# ASIC_2.net
KiCad netlist of a schematic drawn in Altium Designer
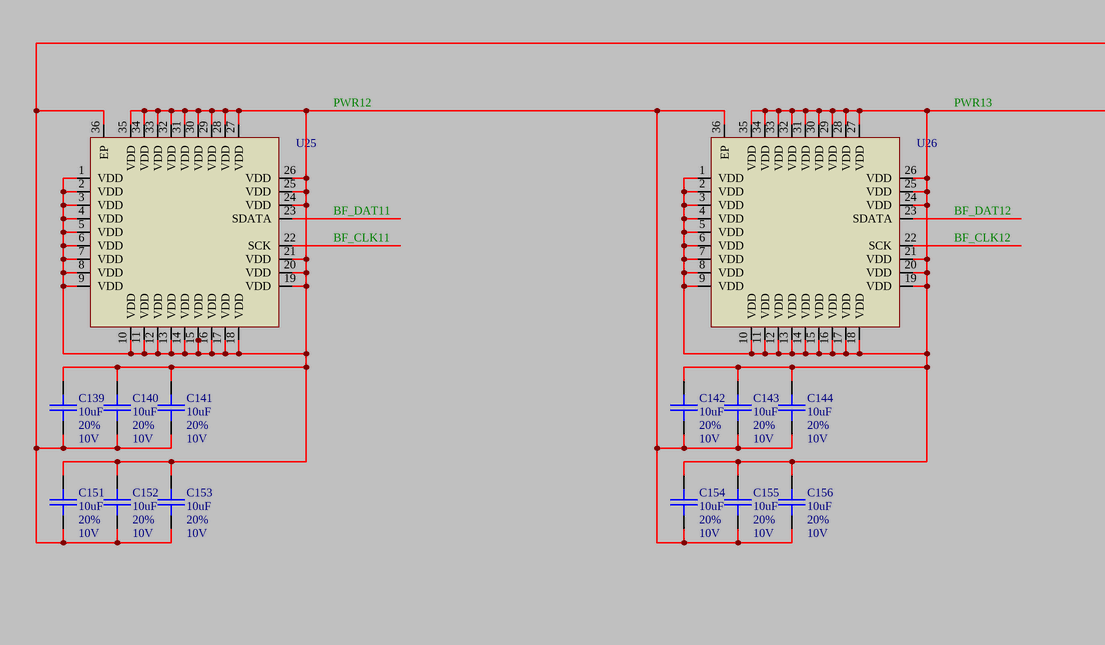
[diagram p0: ASIC_2.SchDoc, left]
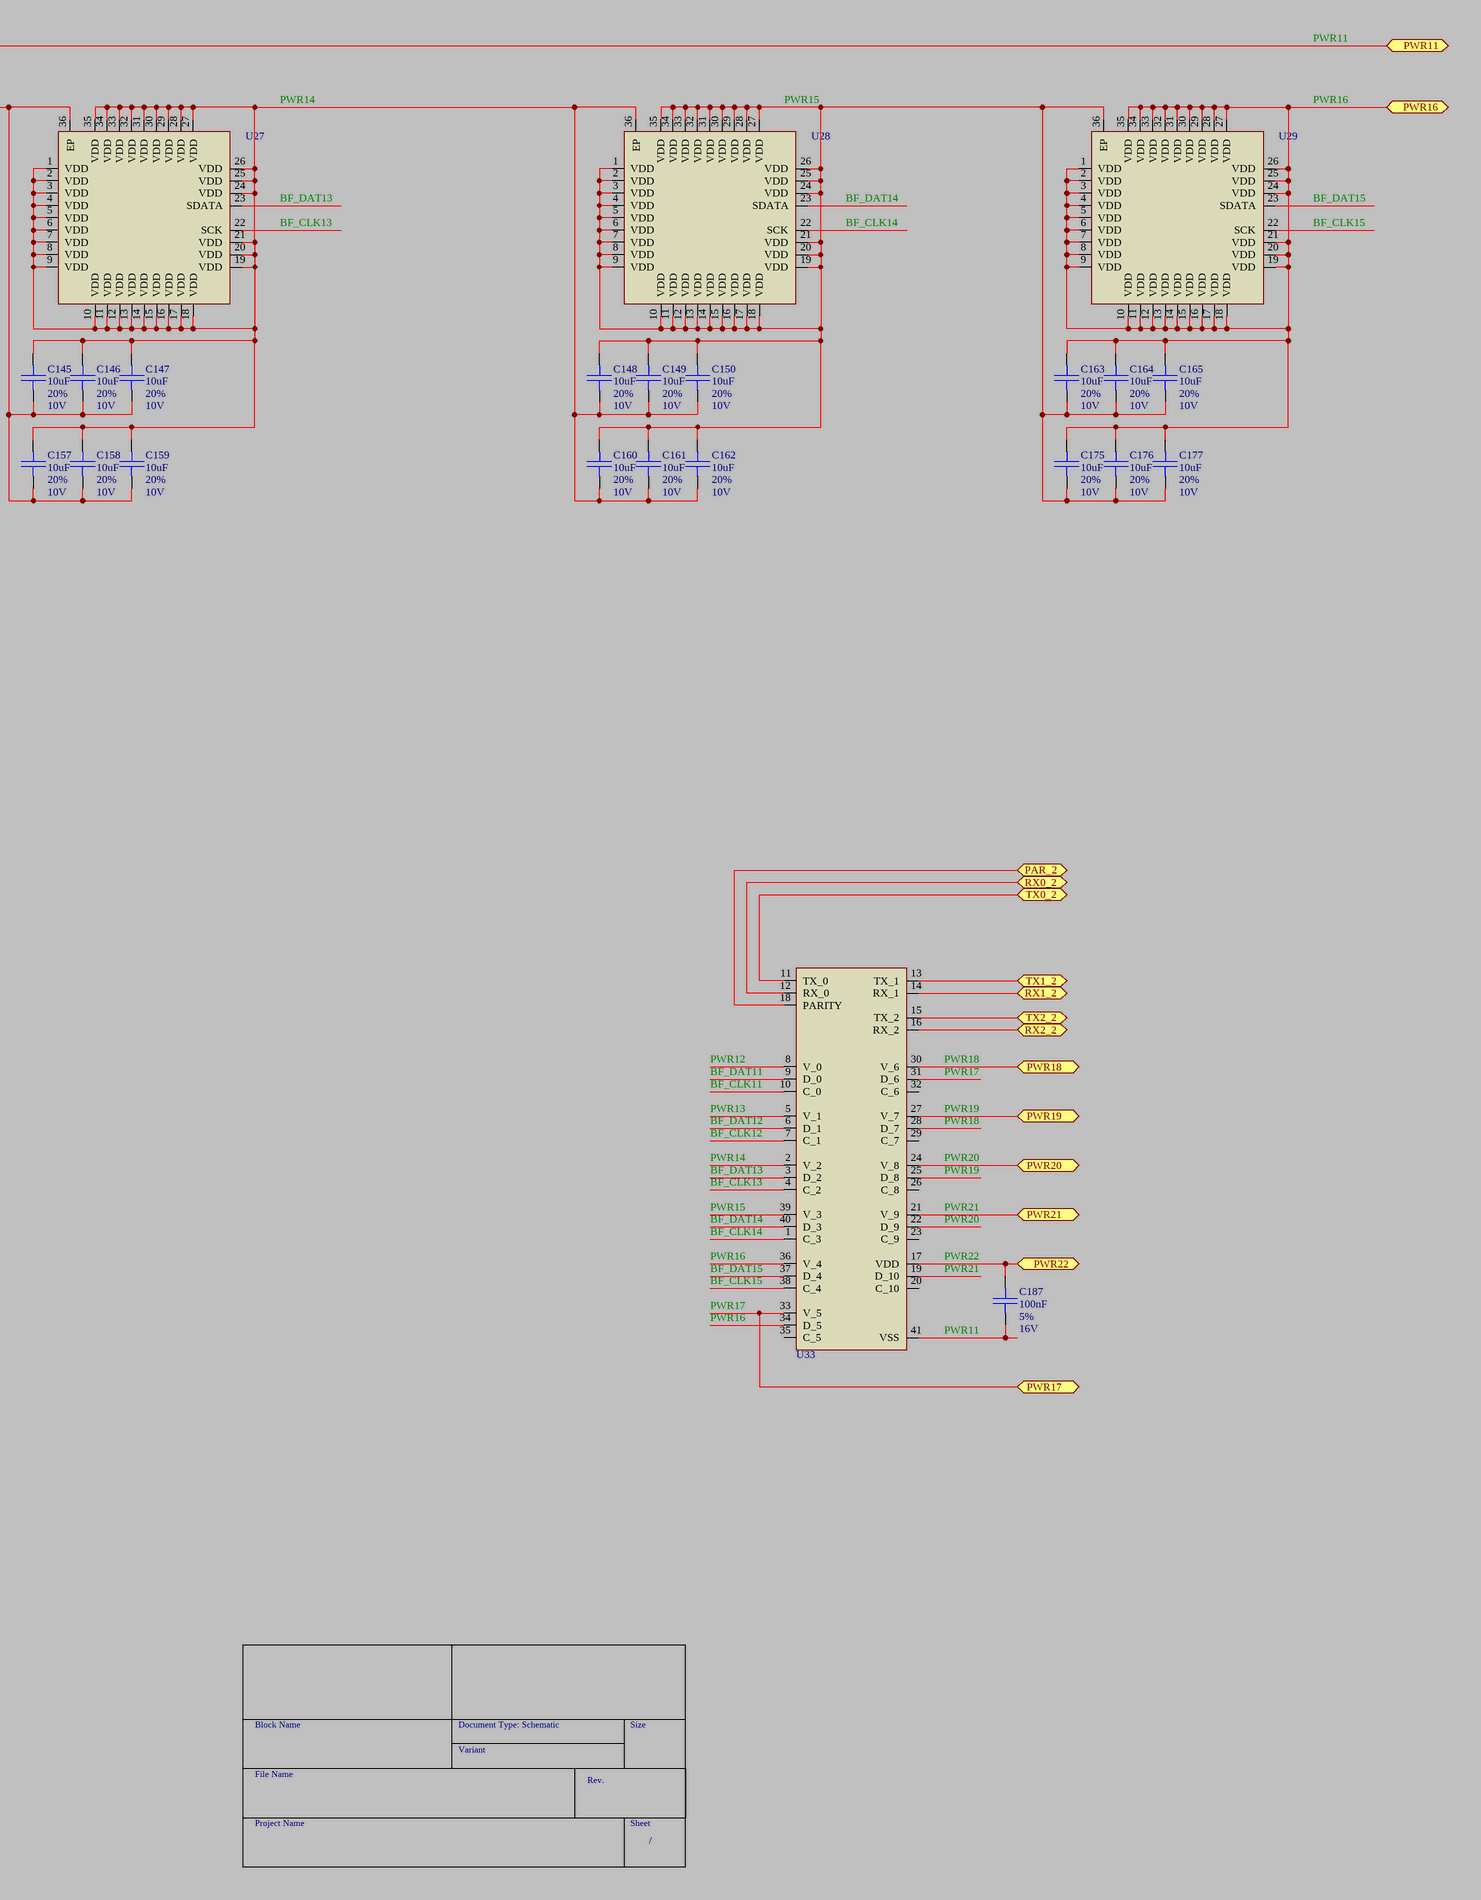
[diagram p1: ASIC_2.SchDoc, right]

(export (version "E")
  (design (tool "Eeschema 10.0.6"))
  (components
    (comp (ref "C139")
      (value "C")
      (footprint "SMD_0402_CAPC1005X70N")
      (fields
        (field (name "DB_PART_NUMBER") "CAP000047481")
        (field (name "DB_VALUE") "10uF")
        (field (name "DB_TOLERANCE") "20%")
        (field (name "DB_VOLTAGE") "10V")
        (field (name "DB_MANUFACTURER_PART") "SAMSUNG    CL05A106MP5NUNC")
        (field (name "DB_APPROVED_BY") "VSN")
      )
      (libsource (lib "Database_Libs1") (part "C"))
    )
    (comp (ref "C140")
      (value "C")
      (footprint "SMD_0402_CAPC1005X70N")
      (fields
        (field (name "DB_PART_NUMBER") "CAP000047481")
        (field (name "DB_VALUE") "10uF")
        (field (name "DB_TOLERANCE") "20%")
        (field (name "DB_VOLTAGE") "10V")
        (field (name "DB_MANUFACTURER_PART") "SAMSUNG    CL05A106MP5NUNC")
        (field (name "DB_APPROVED_BY") "VSN")
      )
      (libsource (lib "Database_Libs1") (part "C"))
    )
    (comp (ref "C141")
      (value "C")
      (footprint "SMD_0402_CAPC1005X70N")
      (fields
        (field (name "DB_PART_NUMBER") "CAP000047481")
        (field (name "DB_VALUE") "10uF")
        (field (name "DB_TOLERANCE") "20%")
        (field (name "DB_VOLTAGE") "10V")
        (field (name "DB_MANUFACTURER_PART") "SAMSUNG    CL05A106MP5NUNC")
        (field (name "DB_APPROVED_BY") "VSN")
      )
      (libsource (lib "Database_Libs1") (part "C"))
    )
    (comp (ref "C142")
      (value "C")
      (footprint "SMD_0402_CAPC1005X70N")
      (fields
        (field (name "DB_PART_NUMBER") "CAP000047481")
        (field (name "DB_VALUE") "10uF")
        (field (name "DB_TOLERANCE") "20%")
        (field (name "DB_VOLTAGE") "10V")
        (field (name "DB_MANUFACTURER_PART") "SAMSUNG    CL05A106MP5NUNC")
        (field (name "DB_APPROVED_BY") "VSN")
      )
      (libsource (lib "Database_Libs1") (part "C"))
    )
    (comp (ref "C143")
      (value "C")
      (footprint "SMD_0402_CAPC1005X70N")
      (fields
        (field (name "DB_PART_NUMBER") "CAP000047481")
        (field (name "DB_VALUE") "10uF")
        (field (name "DB_TOLERANCE") "20%")
        (field (name "DB_VOLTAGE") "10V")
        (field (name "DB_MANUFACTURER_PART") "SAMSUNG    CL05A106MP5NUNC")
        (field (name "DB_APPROVED_BY") "VSN")
      )
      (libsource (lib "Database_Libs1") (part "C"))
    )
    (comp (ref "C144")
      (value "C")
      (footprint "SMD_0402_CAPC1005X70N")
      (fields
        (field (name "DB_PART_NUMBER") "CAP000047481")
        (field (name "DB_VALUE") "10uF")
        (field (name "DB_TOLERANCE") "20%")
        (field (name "DB_VOLTAGE") "10V")
        (field (name "DB_MANUFACTURER_PART") "SAMSUNG    CL05A106MP5NUNC")
        (field (name "DB_APPROVED_BY") "VSN")
      )
      (libsource (lib "Database_Libs1") (part "C"))
    )
    (comp (ref "C145")
      (value "C")
      (footprint "SMD_0402_CAPC1005X70N")
      (fields
        (field (name "DB_PART_NUMBER") "CAP000047481")
        (field (name "DB_VALUE") "10uF")
        (field (name "DB_TOLERANCE") "20%")
        (field (name "DB_VOLTAGE") "10V")
        (field (name "DB_MANUFACTURER_PART") "SAMSUNG    CL05A106MP5NUNC")
        (field (name "DB_APPROVED_BY") "VSN")
      )
      (libsource (lib "Database_Libs1") (part "C"))
    )
    (comp (ref "C146")
      (value "C")
      (footprint "SMD_0402_CAPC1005X70N")
      (fields
        (field (name "DB_PART_NUMBER") "CAP000047481")
        (field (name "DB_VALUE") "10uF")
        (field (name "DB_TOLERANCE") "20%")
        (field (name "DB_VOLTAGE") "10V")
        (field (name "DB_MANUFACTURER_PART") "SAMSUNG    CL05A106MP5NUNC")
        (field (name "DB_APPROVED_BY") "VSN")
      )
      (libsource (lib "Database_Libs1") (part "C"))
    )
    (comp (ref "C147")
      (value "C")
      (footprint "SMD_0402_CAPC1005X70N")
      (fields
        (field (name "DB_PART_NUMBER") "CAP000047481")
        (field (name "DB_VALUE") "10uF")
        (field (name "DB_TOLERANCE") "20%")
        (field (name "DB_VOLTAGE") "10V")
        (field (name "DB_MANUFACTURER_PART") "SAMSUNG    CL05A106MP5NUNC")
        (field (name "DB_APPROVED_BY") "VSN")
      )
      (libsource (lib "Database_Libs1") (part "C"))
    )
    (comp (ref "C148")
      (value "C")
      (footprint "SMD_0402_CAPC1005X70N")
      (fields
        (field (name "DB_PART_NUMBER") "CAP000047481")
        (field (name "DB_VALUE") "10uF")
        (field (name "DB_TOLERANCE") "20%")
        (field (name "DB_VOLTAGE") "10V")
        (field (name "DB_MANUFACTURER_PART") "SAMSUNG    CL05A106MP5NUNC")
        (field (name "DB_APPROVED_BY") "VSN")
      )
      (libsource (lib "Database_Libs1") (part "C"))
    )
    (comp (ref "C149")
      (value "C")
      (footprint "SMD_0402_CAPC1005X70N")
      (fields
        (field (name "DB_PART_NUMBER") "CAP000047481")
        (field (name "DB_VALUE") "10uF")
        (field (name "DB_TOLERANCE") "20%")
        (field (name "DB_VOLTAGE") "10V")
        (field (name "DB_MANUFACTURER_PART") "SAMSUNG    CL05A106MP5NUNC")
        (field (name "DB_APPROVED_BY") "VSN")
      )
      (libsource (lib "Database_Libs1") (part "C"))
    )
    (comp (ref "C150")
      (value "C")
      (footprint "SMD_0402_CAPC1005X70N")
      (fields
        (field (name "DB_PART_NUMBER") "CAP000047481")
        (field (name "DB_VALUE") "10uF")
        (field (name "DB_TOLERANCE") "20%")
        (field (name "DB_VOLTAGE") "10V")
        (field (name "DB_MANUFACTURER_PART") "SAMSUNG    CL05A106MP5NUNC")
        (field (name "DB_APPROVED_BY") "VSN")
      )
      (libsource (lib "Database_Libs1") (part "C"))
    )
    (comp (ref "C151")
      (value "C")
      (footprint "SMD_0402_CAPC1005X70N")
      (fields
        (field (name "DB_PART_NUMBER") "CAP000047481")
        (field (name "DB_VALUE") "10uF")
        (field (name "DB_TOLERANCE") "20%")
        (field (name "DB_VOLTAGE") "10V")
        (field (name "DB_MANUFACTURER_PART") "SAMSUNG    CL05A106MP5NUNC")
        (field (name "DB_APPROVED_BY") "VSN")
      )
      (libsource (lib "Database_Libs1") (part "C"))
    )
    (comp (ref "C152")
      (value "C")
      (footprint "SMD_0402_CAPC1005X70N")
      (fields
        (field (name "DB_PART_NUMBER") "CAP000047481")
        (field (name "DB_VALUE") "10uF")
        (field (name "DB_TOLERANCE") "20%")
        (field (name "DB_VOLTAGE") "10V")
        (field (name "DB_MANUFACTURER_PART") "SAMSUNG    CL05A106MP5NUNC")
        (field (name "DB_APPROVED_BY") "VSN")
      )
      (libsource (lib "Database_Libs1") (part "C"))
    )
    (comp (ref "C153")
      (value "C")
      (footprint "SMD_0402_CAPC1005X70N")
      (fields
        (field (name "DB_PART_NUMBER") "CAP000047481")
        (field (name "DB_VALUE") "10uF")
        (field (name "DB_TOLERANCE") "20%")
        (field (name "DB_VOLTAGE") "10V")
        (field (name "DB_MANUFACTURER_PART") "SAMSUNG    CL05A106MP5NUNC")
        (field (name "DB_APPROVED_BY") "VSN")
      )
      (libsource (lib "Database_Libs1") (part "C"))
    )
    (comp (ref "C154")
      (value "C")
      (footprint "SMD_0402_CAPC1005X70N")
      (fields
        (field (name "DB_PART_NUMBER") "CAP000047481")
        (field (name "DB_VALUE") "10uF")
        (field (name "DB_TOLERANCE") "20%")
        (field (name "DB_VOLTAGE") "10V")
        (field (name "DB_MANUFACTURER_PART") "SAMSUNG    CL05A106MP5NUNC")
        (field (name "DB_APPROVED_BY") "VSN")
      )
      (libsource (lib "Database_Libs1") (part "C"))
    )
    (comp (ref "C155")
      (value "C")
      (footprint "SMD_0402_CAPC1005X70N")
      (fields
        (field (name "DB_PART_NUMBER") "CAP000047481")
        (field (name "DB_VALUE") "10uF")
        (field (name "DB_TOLERANCE") "20%")
        (field (name "DB_VOLTAGE") "10V")
        (field (name "DB_MANUFACTURER_PART") "SAMSUNG    CL05A106MP5NUNC")
        (field (name "DB_APPROVED_BY") "VSN")
      )
      (libsource (lib "Database_Libs1") (part "C"))
    )
    (comp (ref "C156")
      (value "C")
      (footprint "SMD_0402_CAPC1005X70N")
      (fields
        (field (name "DB_PART_NUMBER") "CAP000047481")
        (field (name "DB_VALUE") "10uF")
        (field (name "DB_TOLERANCE") "20%")
        (field (name "DB_VOLTAGE") "10V")
        (field (name "DB_MANUFACTURER_PART") "SAMSUNG    CL05A106MP5NUNC")
        (field (name "DB_APPROVED_BY") "VSN")
      )
      (libsource (lib "Database_Libs1") (part "C"))
    )
    (comp (ref "C157")
      (value "C")
      (footprint "SMD_0402_CAPC1005X70N")
      (fields
        (field (name "DB_PART_NUMBER") "CAP000047481")
        (field (name "DB_VALUE") "10uF")
        (field (name "DB_TOLERANCE") "20%")
        (field (name "DB_VOLTAGE") "10V")
        (field (name "DB_MANUFACTURER_PART") "SAMSUNG    CL05A106MP5NUNC")
        (field (name "DB_APPROVED_BY") "VSN")
      )
      (libsource (lib "Database_Libs1") (part "C"))
    )
    (comp (ref "C158")
      (value "C")
      (footprint "SMD_0402_CAPC1005X70N")
      (fields
        (field (name "DB_PART_NUMBER") "CAP000047481")
        (field (name "DB_VALUE") "10uF")
        (field (name "DB_TOLERANCE") "20%")
        (field (name "DB_VOLTAGE") "10V")
        (field (name "DB_MANUFACTURER_PART") "SAMSUNG    CL05A106MP5NUNC")
        (field (name "DB_APPROVED_BY") "VSN")
      )
      (libsource (lib "Database_Libs1") (part "C"))
    )
    (comp (ref "C159")
      (value "C")
      (footprint "SMD_0402_CAPC1005X70N")
      (fields
        (field (name "DB_PART_NUMBER") "CAP000047481")
        (field (name "DB_VALUE") "10uF")
        (field (name "DB_TOLERANCE") "20%")
        (field (name "DB_VOLTAGE") "10V")
        (field (name "DB_MANUFACTURER_PART") "SAMSUNG    CL05A106MP5NUNC")
        (field (name "DB_APPROVED_BY") "VSN")
      )
      (libsource (lib "Database_Libs1") (part "C"))
    )
    (comp (ref "C160")
      (value "C")
      (footprint "SMD_0402_CAPC1005X70N")
      (fields
        (field (name "DB_PART_NUMBER") "CAP000047481")
        (field (name "DB_VALUE") "10uF")
        (field (name "DB_TOLERANCE") "20%")
        (field (name "DB_VOLTAGE") "10V")
        (field (name "DB_MANUFACTURER_PART") "SAMSUNG    CL05A106MP5NUNC")
        (field (name "DB_APPROVED_BY") "VSN")
      )
      (libsource (lib "Database_Libs1") (part "C"))
    )
    (comp (ref "C161")
      (value "C")
      (footprint "SMD_0402_CAPC1005X70N")
      (fields
        (field (name "DB_PART_NUMBER") "CAP000047481")
        (field (name "DB_VALUE") "10uF")
        (field (name "DB_TOLERANCE") "20%")
        (field (name "DB_VOLTAGE") "10V")
        (field (name "DB_MANUFACTURER_PART") "SAMSUNG    CL05A106MP5NUNC")
        (field (name "DB_APPROVED_BY") "VSN")
      )
      (libsource (lib "Database_Libs1") (part "C"))
    )
    (comp (ref "C162")
      (value "C")
      (footprint "SMD_0402_CAPC1005X70N")
      (fields
        (field (name "DB_PART_NUMBER") "CAP000047481")
        (field (name "DB_VALUE") "10uF")
        (field (name "DB_TOLERANCE") "20%")
        (field (name "DB_VOLTAGE") "10V")
        (field (name "DB_MANUFACTURER_PART") "SAMSUNG    CL05A106MP5NUNC")
        (field (name "DB_APPROVED_BY") "VSN")
      )
      (libsource (lib "Database_Libs1") (part "C"))
    )
    (comp (ref "C163")
      (value "C")
      (footprint "SMD_0402_CAPC1005X70N")
      (fields
        (field (name "DB_PART_NUMBER") "CAP000047481")
        (field (name "DB_VALUE") "10uF")
        (field (name "DB_TOLERANCE") "20%")
        (field (name "DB_VOLTAGE") "10V")
        (field (name "DB_MANUFACTURER_PART") "SAMSUNG    CL05A106MP5NUNC")
        (field (name "DB_APPROVED_BY") "VSN")
      )
      (libsource (lib "Database_Libs1") (part "C"))
    )
    (comp (ref "C164")
      (value "C")
      (footprint "SMD_0402_CAPC1005X70N")
      (fields
        (field (name "DB_PART_NUMBER") "CAP000047481")
        (field (name "DB_VALUE") "10uF")
        (field (name "DB_TOLERANCE") "20%")
        (field (name "DB_VOLTAGE") "10V")
        (field (name "DB_MANUFACTURER_PART") "SAMSUNG    CL05A106MP5NUNC")
        (field (name "DB_APPROVED_BY") "VSN")
      )
      (libsource (lib "Database_Libs1") (part "C"))
    )
    (comp (ref "C165")
      (value "C")
      (footprint "SMD_0402_CAPC1005X70N")
      (fields
        (field (name "DB_PART_NUMBER") "CAP000047481")
        (field (name "DB_VALUE") "10uF")
        (field (name "DB_TOLERANCE") "20%")
        (field (name "DB_VOLTAGE") "10V")
        (field (name "DB_MANUFACTURER_PART") "SAMSUNG    CL05A106MP5NUNC")
        (field (name "DB_APPROVED_BY") "VSN")
      )
      (libsource (lib "Database_Libs1") (part "C"))
    )
    (comp (ref "C175")
      (value "C")
      (footprint "SMD_0402_CAPC1005X70N")
      (fields
        (field (name "DB_PART_NUMBER") "CAP000047481")
        (field (name "DB_VALUE") "10uF")
        (field (name "DB_TOLERANCE") "20%")
        (field (name "DB_VOLTAGE") "10V")
        (field (name "DB_MANUFACTURER_PART") "SAMSUNG    CL05A106MP5NUNC")
        (field (name "DB_APPROVED_BY") "VSN")
      )
      (libsource (lib "Database_Libs1") (part "C"))
    )
    (comp (ref "C176")
      (value "C")
      (footprint "SMD_0402_CAPC1005X70N")
      (fields
        (field (name "DB_PART_NUMBER") "CAP000047481")
        (field (name "DB_VALUE") "10uF")
        (field (name "DB_TOLERANCE") "20%")
        (field (name "DB_VOLTAGE") "10V")
        (field (name "DB_MANUFACTURER_PART") "SAMSUNG    CL05A106MP5NUNC")
        (field (name "DB_APPROVED_BY") "VSN")
      )
      (libsource (lib "Database_Libs1") (part "C"))
    )
    (comp (ref "C177")
      (value "C")
      (footprint "SMD_0402_CAPC1005X70N")
      (fields
        (field (name "DB_PART_NUMBER") "CAP000047481")
        (field (name "DB_VALUE") "10uF")
        (field (name "DB_TOLERANCE") "20%")
        (field (name "DB_VOLTAGE") "10V")
        (field (name "DB_MANUFACTURER_PART") "SAMSUNG    CL05A106MP5NUNC")
        (field (name "DB_APPROVED_BY") "VSN")
      )
      (libsource (lib "Database_Libs1") (part "C"))
    )
    (comp (ref "C187")
      (value "C")
      (footprint "SMD_0603_CAPC1608X95N")
      (fields
        (field (name "DB_PART_NUMBER") "CAP000027134")
        (field (name "DB_VALUE") "100nF")
        (field (name "DB_TOLERANCE") "5%")
        (field (name "DB_VOLTAGE") "16V")
        (field (name "DB_MANUFACTURER_PART") "KEMET    C0603C104J4RAC")
      )
      (libsource (lib "Database_Libs1") (part "C"))
    )
    (comp (ref "U25")
      (value "IC_BITFURY16")
      (footprint "SMD_QFN50P600X600X175-36AN")
      (description "BitFury 2016 16 nm")
      (libsource (lib "BitCoin") (part "IC_BITFURY16"))
    )
    (comp (ref "U26")
      (value "IC_BITFURY16")
      (footprint "SMD_QFN50P600X600X175-36AN")
      (description "BitFury 2016 16 nm")
      (libsource (lib "BitCoin") (part "IC_BITFURY16"))
    )
    (comp (ref "U27")
      (value "IC_BITFURY16")
      (footprint "SMD_QFN50P600X600X175-36AN")
      (description "BitFury 2016 16 nm")
      (libsource (lib "BitCoin") (part "IC_BITFURY16"))
    )
    (comp (ref "U28")
      (value "IC_BITFURY16")
      (footprint "SMD_QFN50P600X600X175-36AN")
      (description "BitFury 2016 16 nm")
      (libsource (lib "BitCoin") (part "IC_BITFURY16"))
    )
    (comp (ref "U29")
      (value "IC_BITFURY16")
      (footprint "SMD_QFN50P600X600X175-36AN")
      (description "BitFury 2016 16 nm")
      (libsource (lib "BitCoin") (part "IC_BITFURY16"))
    )
    (comp (ref "U33")
      (value "IC_BTC250")
      (footprint "SMD_QFN40P500X500X80-41N")
      (fields (field (name "DB_MANUFACTURER_PART") "BTC250 QFN40 EP"))
      (libsource (lib "BitCoin") (part "IC_BTC250"))
    )
  )
  (nets
    (net (code "1") (name "/BF_CLK11") (class "Default")
      (node (ref "U25") (pin "22") (pinfunction "SCK_22") (pintype "passive"))
      (node (ref "U33") (pin "10") (pinfunction "C_0_10") (pintype "passive"))
    )
    (net (code "2") (name "/BF_CLK12") (class "Default")
      (node (ref "U26") (pin "22") (pinfunction "SCK_22") (pintype "passive"))
      (node (ref "U33") (pin "7") (pinfunction "C_1_7") (pintype "passive"))
    )
    (net (code "3") (name "/BF_CLK13") (class "Default")
      (node (ref "U27") (pin "22") (pinfunction "SCK_22") (pintype "passive"))
      (node (ref "U33") (pin "4") (pinfunction "C_2_4") (pintype "passive"))
    )
    (net (code "4") (name "/BF_CLK14") (class "Default")
      (node (ref "U28") (pin "22") (pinfunction "SCK_22") (pintype "passive"))
      (node (ref "U33") (pin "1") (pinfunction "C_3_1") (pintype "passive"))
    )
    (net (code "5") (name "/BF_CLK15") (class "Default")
      (node (ref "U29") (pin "22") (pinfunction "SCK_22") (pintype "passive"))
      (node (ref "U33") (pin "38") (pinfunction "C_4_38") (pintype "passive"))
    )
    (net (code "6") (name "/BF_DAT11") (class "Default")
      (node (ref "U25") (pin "23") (pinfunction "SDATA_23") (pintype "passive"))
      (node (ref "U33") (pin "9") (pinfunction "D_0_9") (pintype "passive"))
    )
    (net (code "7") (name "/BF_DAT12") (class "Default")
      (node (ref "U26") (pin "23") (pinfunction "SDATA_23") (pintype "passive"))
      (node (ref "U33") (pin "6") (pinfunction "D_1_6") (pintype "passive"))
    )
    (net (code "8") (name "/BF_DAT13") (class "Default")
      (node (ref "U27") (pin "23") (pinfunction "SDATA_23") (pintype "passive"))
      (node (ref "U33") (pin "3") (pinfunction "D_2_3") (pintype "passive"))
    )
    (net (code "9") (name "/BF_DAT14") (class "Default")
      (node (ref "U28") (pin "23") (pinfunction "SDATA_23") (pintype "passive"))
      (node (ref "U33") (pin "40") (pinfunction "D_3_40") (pintype "passive"))
    )
    (net (code "10") (name "/BF_DAT15") (class "Default")
      (node (ref "U29") (pin "23") (pinfunction "SDATA_23") (pintype "passive"))
      (node (ref "U33") (pin "37") (pinfunction "D_4_37") (pintype "passive"))
    )
    (net (code "11") (name "/PAR_2") (class "Default")
      (node (ref "U33") (pin "18") (pinfunction "PARITY_18") (pintype "passive"))
    )
    (net (code "12") (name "/PWR11") (class "Default")
      (node (ref "C139") (pin "2") (pinfunction "2_2") (pintype "passive"))
      (node (ref "C140") (pin "2") (pinfunction "2_2") (pintype "passive"))
      (node (ref "C141") (pin "2") (pinfunction "2_2") (pintype "passive"))
      (node (ref "C151") (pin "2") (pinfunction "2_2") (pintype "passive"))
      (node (ref "C152") (pin "2") (pinfunction "2_2") (pintype "passive"))
      (node (ref "C153") (pin "2") (pinfunction "2_2") (pintype "passive"))
      (node (ref "C187") (pin "2") (pinfunction "2_2") (pintype "passive"))
      (node (ref "U25") (pin "36") (pinfunction "EP_36") (pintype "passive"))
      (node (ref "U33") (pin "41") (pinfunction "VSS_41") (pintype "passive"))
    )
    (net (code "13") (name "/PWR12") (class "Default")
      (node (ref "C139") (pin "1") (pinfunction "1_1") (pintype "passive"))
      (node (ref "C140") (pin "1") (pinfunction "1_1") (pintype "passive"))
      (node (ref "C141") (pin "1") (pinfunction "1_1") (pintype "passive"))
      (node (ref "C142") (pin "2") (pinfunction "2_2") (pintype "passive"))
      (node (ref "C143") (pin "2") (pinfunction "2_2") (pintype "passive"))
      (node (ref "C144") (pin "2") (pinfunction "2_2") (pintype "passive"))
      (node (ref "C151") (pin "1") (pinfunction "1_1") (pintype "passive"))
      (node (ref "C152") (pin "1") (pinfunction "1_1") (pintype "passive"))
      (node (ref "C153") (pin "1") (pinfunction "1_1") (pintype "passive"))
      (node (ref "C154") (pin "2") (pinfunction "2_2") (pintype "passive"))
      (node (ref "C155") (pin "2") (pinfunction "2_2") (pintype "passive"))
      (node (ref "C156") (pin "2") (pinfunction "2_2") (pintype "passive"))
      (node (ref "U25") (pin "1") (pinfunction "VDD_1") (pintype "passive"))
      (node (ref "U25") (pin "10") (pinfunction "VDD_10") (pintype "passive"))
      (node (ref "U25") (pin "11") (pinfunction "VDD_11") (pintype "passive"))
      (node (ref "U25") (pin "12") (pinfunction "VDD_12") (pintype "passive"))
      (node (ref "U25") (pin "13") (pinfunction "VDD_13") (pintype "passive"))
      (node (ref "U25") (pin "14") (pinfunction "VDD_14") (pintype "passive"))
      (node (ref "U25") (pin "15") (pinfunction "VDD_15") (pintype "passive"))
      (node (ref "U25") (pin "16") (pinfunction "VDD_16") (pintype "passive"))
      (node (ref "U25") (pin "17") (pinfunction "VDD_17") (pintype "passive"))
      (node (ref "U25") (pin "18") (pinfunction "VDD_18") (pintype "passive"))
      (node (ref "U25") (pin "19") (pinfunction "VDD_19") (pintype "passive"))
      (node (ref "U25") (pin "2") (pinfunction "VDD_2") (pintype "passive"))
      (node (ref "U25") (pin "20") (pinfunction "VDD_20") (pintype "passive"))
      (node (ref "U25") (pin "21") (pinfunction "VDD_21") (pintype "passive"))
      (node (ref "U25") (pin "24") (pinfunction "VDD_24") (pintype "passive"))
      (node (ref "U25") (pin "25") (pinfunction "VDD_25") (pintype "passive"))
      (node (ref "U25") (pin "26") (pinfunction "VDD_26") (pintype "passive"))
      (node (ref "U25") (pin "27") (pinfunction "VDD_27") (pintype "passive"))
      (node (ref "U25") (pin "28") (pinfunction "VDD_28") (pintype "passive"))
      (node (ref "U25") (pin "29") (pinfunction "VDD_29") (pintype "passive"))
      (node (ref "U25") (pin "3") (pinfunction "VDD_3") (pintype "passive"))
      (node (ref "U25") (pin "30") (pinfunction "VDD_30") (pintype "passive"))
      (node (ref "U25") (pin "31") (pinfunction "VDD_31") (pintype "passive"))
      (node (ref "U25") (pin "32") (pinfunction "VDD_32") (pintype "passive"))
      (node (ref "U25") (pin "33") (pinfunction "VDD_33") (pintype "passive"))
      (node (ref "U25") (pin "34") (pinfunction "VDD_34") (pintype "passive"))
      (node (ref "U25") (pin "35") (pinfunction "VDD_35") (pintype "passive"))
      (node (ref "U25") (pin "4") (pinfunction "VDD_4") (pintype "passive"))
      (node (ref "U25") (pin "5") (pinfunction "VDD_5") (pintype "passive"))
      (node (ref "U25") (pin "6") (pinfunction "VDD_6") (pintype "passive"))
      (node (ref "U25") (pin "7") (pinfunction "VDD_7") (pintype "passive"))
      (node (ref "U25") (pin "8") (pinfunction "VDD_8") (pintype "passive"))
      (node (ref "U25") (pin "9") (pinfunction "VDD_9") (pintype "passive"))
      (node (ref "U26") (pin "36") (pinfunction "EP_36") (pintype "passive"))
      (node (ref "U33") (pin "8") (pinfunction "V_0_8") (pintype "passive"))
    )
    (net (code "14") (name "/PWR13") (class "Default")
      (node (ref "C142") (pin "1") (pinfunction "1_1") (pintype "passive"))
      (node (ref "C143") (pin "1") (pinfunction "1_1") (pintype "passive"))
      (node (ref "C144") (pin "1") (pinfunction "1_1") (pintype "passive"))
      (node (ref "C145") (pin "2") (pinfunction "2_2") (pintype "passive"))
      (node (ref "C146") (pin "2") (pinfunction "2_2") (pintype "passive"))
      (node (ref "C147") (pin "2") (pinfunction "2_2") (pintype "passive"))
      (node (ref "C154") (pin "1") (pinfunction "1_1") (pintype "passive"))
      (node (ref "C155") (pin "1") (pinfunction "1_1") (pintype "passive"))
      (node (ref "C156") (pin "1") (pinfunction "1_1") (pintype "passive"))
      (node (ref "C157") (pin "2") (pinfunction "2_2") (pintype "passive"))
      (node (ref "C158") (pin "2") (pinfunction "2_2") (pintype "passive"))
      (node (ref "C159") (pin "2") (pinfunction "2_2") (pintype "passive"))
      (node (ref "U26") (pin "1") (pinfunction "VDD_1") (pintype "passive"))
      (node (ref "U26") (pin "10") (pinfunction "VDD_10") (pintype "passive"))
      (node (ref "U26") (pin "11") (pinfunction "VDD_11") (pintype "passive"))
      (node (ref "U26") (pin "12") (pinfunction "VDD_12") (pintype "passive"))
      (node (ref "U26") (pin "13") (pinfunction "VDD_13") (pintype "passive"))
      (node (ref "U26") (pin "14") (pinfunction "VDD_14") (pintype "passive"))
      (node (ref "U26") (pin "15") (pinfunction "VDD_15") (pintype "passive"))
      (node (ref "U26") (pin "16") (pinfunction "VDD_16") (pintype "passive"))
      (node (ref "U26") (pin "17") (pinfunction "VDD_17") (pintype "passive"))
      (node (ref "U26") (pin "18") (pinfunction "VDD_18") (pintype "passive"))
      (node (ref "U26") (pin "19") (pinfunction "VDD_19") (pintype "passive"))
      (node (ref "U26") (pin "2") (pinfunction "VDD_2") (pintype "passive"))
      (node (ref "U26") (pin "20") (pinfunction "VDD_20") (pintype "passive"))
      (node (ref "U26") (pin "21") (pinfunction "VDD_21") (pintype "passive"))
      (node (ref "U26") (pin "24") (pinfunction "VDD_24") (pintype "passive"))
      (node (ref "U26") (pin "25") (pinfunction "VDD_25") (pintype "passive"))
      (node (ref "U26") (pin "26") (pinfunction "VDD_26") (pintype "passive"))
      (node (ref "U26") (pin "27") (pinfunction "VDD_27") (pintype "passive"))
      (node (ref "U26") (pin "28") (pinfunction "VDD_28") (pintype "passive"))
      (node (ref "U26") (pin "29") (pinfunction "VDD_29") (pintype "passive"))
      (node (ref "U26") (pin "3") (pinfunction "VDD_3") (pintype "passive"))
      (node (ref "U26") (pin "30") (pinfunction "VDD_30") (pintype "passive"))
      (node (ref "U26") (pin "31") (pinfunction "VDD_31") (pintype "passive"))
      (node (ref "U26") (pin "32") (pinfunction "VDD_32") (pintype "passive"))
      (node (ref "U26") (pin "33") (pinfunction "VDD_33") (pintype "passive"))
      (node (ref "U26") (pin "34") (pinfunction "VDD_34") (pintype "passive"))
      (node (ref "U26") (pin "35") (pinfunction "VDD_35") (pintype "passive"))
      (node (ref "U26") (pin "4") (pinfunction "VDD_4") (pintype "passive"))
      (node (ref "U26") (pin "5") (pinfunction "VDD_5") (pintype "passive"))
      (node (ref "U26") (pin "6") (pinfunction "VDD_6") (pintype "passive"))
      (node (ref "U26") (pin "7") (pinfunction "VDD_7") (pintype "passive"))
      (node (ref "U26") (pin "8") (pinfunction "VDD_8") (pintype "passive"))
      (node (ref "U26") (pin "9") (pinfunction "VDD_9") (pintype "passive"))
      (node (ref "U27") (pin "36") (pinfunction "EP_36") (pintype "passive"))
      (node (ref "U33") (pin "5") (pinfunction "V_1_5") (pintype "passive"))
    )
    (net (code "15") (name "/PWR14") (class "Default")
      (node (ref "C145") (pin "1") (pinfunction "1_1") (pintype "passive"))
      (node (ref "C146") (pin "1") (pinfunction "1_1") (pintype "passive"))
      (node (ref "C147") (pin "1") (pinfunction "1_1") (pintype "passive"))
      (node (ref "C148") (pin "2") (pinfunction "2_2") (pintype "passive"))
      (node (ref "C149") (pin "2") (pinfunction "2_2") (pintype "passive"))
      (node (ref "C150") (pin "2") (pinfunction "2_2") (pintype "passive"))
      (node (ref "C157") (pin "1") (pinfunction "1_1") (pintype "passive"))
      (node (ref "C158") (pin "1") (pinfunction "1_1") (pintype "passive"))
      (node (ref "C159") (pin "1") (pinfunction "1_1") (pintype "passive"))
      (node (ref "C160") (pin "2") (pinfunction "2_2") (pintype "passive"))
      (node (ref "C161") (pin "2") (pinfunction "2_2") (pintype "passive"))
      (node (ref "C162") (pin "2") (pinfunction "2_2") (pintype "passive"))
      (node (ref "U27") (pin "1") (pinfunction "VDD_1") (pintype "passive"))
      (node (ref "U27") (pin "10") (pinfunction "VDD_10") (pintype "passive"))
      (node (ref "U27") (pin "11") (pinfunction "VDD_11") (pintype "passive"))
      (node (ref "U27") (pin "12") (pinfunction "VDD_12") (pintype "passive"))
      (node (ref "U27") (pin "13") (pinfunction "VDD_13") (pintype "passive"))
      (node (ref "U27") (pin "14") (pinfunction "VDD_14") (pintype "passive"))
      (node (ref "U27") (pin "15") (pinfunction "VDD_15") (pintype "passive"))
      (node (ref "U27") (pin "16") (pinfunction "VDD_16") (pintype "passive"))
      (node (ref "U27") (pin "17") (pinfunction "VDD_17") (pintype "passive"))
      (node (ref "U27") (pin "18") (pinfunction "VDD_18") (pintype "passive"))
      (node (ref "U27") (pin "19") (pinfunction "VDD_19") (pintype "passive"))
      (node (ref "U27") (pin "2") (pinfunction "VDD_2") (pintype "passive"))
      (node (ref "U27") (pin "20") (pinfunction "VDD_20") (pintype "passive"))
      (node (ref "U27") (pin "21") (pinfunction "VDD_21") (pintype "passive"))
      (node (ref "U27") (pin "24") (pinfunction "VDD_24") (pintype "passive"))
      (node (ref "U27") (pin "25") (pinfunction "VDD_25") (pintype "passive"))
      (node (ref "U27") (pin "26") (pinfunction "VDD_26") (pintype "passive"))
      (node (ref "U27") (pin "27") (pinfunction "VDD_27") (pintype "passive"))
      (node (ref "U27") (pin "28") (pinfunction "VDD_28") (pintype "passive"))
      (node (ref "U27") (pin "29") (pinfunction "VDD_29") (pintype "passive"))
      (node (ref "U27") (pin "3") (pinfunction "VDD_3") (pintype "passive"))
      (node (ref "U27") (pin "30") (pinfunction "VDD_30") (pintype "passive"))
      (node (ref "U27") (pin "31") (pinfunction "VDD_31") (pintype "passive"))
      (node (ref "U27") (pin "32") (pinfunction "VDD_32") (pintype "passive"))
      (node (ref "U27") (pin "33") (pinfunction "VDD_33") (pintype "passive"))
      (node (ref "U27") (pin "34") (pinfunction "VDD_34") (pintype "passive"))
      (node (ref "U27") (pin "35") (pinfunction "VDD_35") (pintype "passive"))
      (node (ref "U27") (pin "4") (pinfunction "VDD_4") (pintype "passive"))
      (node (ref "U27") (pin "5") (pinfunction "VDD_5") (pintype "passive"))
      (node (ref "U27") (pin "6") (pinfunction "VDD_6") (pintype "passive"))
      (node (ref "U27") (pin "7") (pinfunction "VDD_7") (pintype "passive"))
      (node (ref "U27") (pin "8") (pinfunction "VDD_8") (pintype "passive"))
      (node (ref "U27") (pin "9") (pinfunction "VDD_9") (pintype "passive"))
      (node (ref "U28") (pin "36") (pinfunction "EP_36") (pintype "passive"))
      (node (ref "U33") (pin "2") (pinfunction "V_2_2") (pintype "passive"))
    )
    (net (code "16") (name "/PWR15") (class "Default")
      (node (ref "C148") (pin "1") (pinfunction "1_1") (pintype "passive"))
      (node (ref "C149") (pin "1") (pinfunction "1_1") (pintype "passive"))
      (node (ref "C150") (pin "1") (pinfunction "1_1") (pintype "passive"))
      (node (ref "C160") (pin "1") (pinfunction "1_1") (pintype "passive"))
      (node (ref "C161") (pin "1") (pinfunction "1_1") (pintype "passive"))
      (node (ref "C162") (pin "1") (pinfunction "1_1") (pintype "passive"))
      (node (ref "C163") (pin "2") (pinfunction "2_2") (pintype "passive"))
      (node (ref "C164") (pin "2") (pinfunction "2_2") (pintype "passive"))
      (node (ref "C165") (pin "2") (pinfunction "2_2") (pintype "passive"))
      (node (ref "C175") (pin "2") (pinfunction "2_2") (pintype "passive"))
      (node (ref "C176") (pin "2") (pinfunction "2_2") (pintype "passive"))
      (node (ref "C177") (pin "2") (pinfunction "2_2") (pintype "passive"))
      (node (ref "U28") (pin "1") (pinfunction "VDD_1") (pintype "passive"))
      (node (ref "U28") (pin "10") (pinfunction "VDD_10") (pintype "passive"))
      (node (ref "U28") (pin "11") (pinfunction "VDD_11") (pintype "passive"))
      (node (ref "U28") (pin "12") (pinfunction "VDD_12") (pintype "passive"))
      (node (ref "U28") (pin "13") (pinfunction "VDD_13") (pintype "passive"))
      (node (ref "U28") (pin "14") (pinfunction "VDD_14") (pintype "passive"))
      (node (ref "U28") (pin "15") (pinfunction "VDD_15") (pintype "passive"))
      (node (ref "U28") (pin "16") (pinfunction "VDD_16") (pintype "passive"))
      (node (ref "U28") (pin "17") (pinfunction "VDD_17") (pintype "passive"))
      (node (ref "U28") (pin "18") (pinfunction "VDD_18") (pintype "passive"))
      (node (ref "U28") (pin "19") (pinfunction "VDD_19") (pintype "passive"))
      (node (ref "U28") (pin "2") (pinfunction "VDD_2") (pintype "passive"))
      (node (ref "U28") (pin "20") (pinfunction "VDD_20") (pintype "passive"))
      (node (ref "U28") (pin "21") (pinfunction "VDD_21") (pintype "passive"))
      (node (ref "U28") (pin "24") (pinfunction "VDD_24") (pintype "passive"))
      (node (ref "U28") (pin "25") (pinfunction "VDD_25") (pintype "passive"))
      (node (ref "U28") (pin "26") (pinfunction "VDD_26") (pintype "passive"))
      (node (ref "U28") (pin "27") (pinfunction "VDD_27") (pintype "passive"))
      (node (ref "U28") (pin "28") (pinfunction "VDD_28") (pintype "passive"))
      (node (ref "U28") (pin "29") (pinfunction "VDD_29") (pintype "passive"))
      (node (ref "U28") (pin "3") (pinfunction "VDD_3") (pintype "passive"))
      (node (ref "U28") (pin "30") (pinfunction "VDD_30") (pintype "passive"))
      (node (ref "U28") (pin "31") (pinfunction "VDD_31") (pintype "passive"))
      (node (ref "U28") (pin "32") (pinfunction "VDD_32") (pintype "passive"))
      (node (ref "U28") (pin "33") (pinfunction "VDD_33") (pintype "passive"))
      (node (ref "U28") (pin "34") (pinfunction "VDD_34") (pintype "passive"))
      (node (ref "U28") (pin "35") (pinfunction "VDD_35") (pintype "passive"))
      (node (ref "U28") (pin "4") (pinfunction "VDD_4") (pintype "passive"))
      (node (ref "U28") (pin "5") (pinfunction "VDD_5") (pintype "passive"))
      (node (ref "U28") (pin "6") (pinfunction "VDD_6") (pintype "passive"))
      (node (ref "U28") (pin "7") (pinfunction "VDD_7") (pintype "passive"))
      (node (ref "U28") (pin "8") (pinfunction "VDD_8") (pintype "passive"))
      (node (ref "U28") (pin "9") (pinfunction "VDD_9") (pintype "passive"))
      (node (ref "U29") (pin "36") (pinfunction "EP_36") (pintype "passive"))
      (node (ref "U33") (pin "39") (pinfunction "V_3_39") (pintype "passive"))
    )
    (net (code "17") (name "/PWR16") (class "Default")
      (node (ref "C163") (pin "1") (pinfunction "1_1") (pintype "passive"))
      (node (ref "C164") (pin "1") (pinfunction "1_1") (pintype "passive"))
      (node (ref "C165") (pin "1") (pinfunction "1_1") (pintype "passive"))
      (node (ref "C175") (pin "1") (pinfunction "1_1") (pintype "passive"))
      (node (ref "C176") (pin "1") (pinfunction "1_1") (pintype "passive"))
      (node (ref "C177") (pin "1") (pinfunction "1_1") (pintype "passive"))
      (node (ref "U29") (pin "1") (pinfunction "VDD_1") (pintype "passive"))
      (node (ref "U29") (pin "10") (pinfunction "VDD_10") (pintype "passive"))
      (node (ref "U29") (pin "11") (pinfunction "VDD_11") (pintype "passive"))
      (node (ref "U29") (pin "12") (pinfunction "VDD_12") (pintype "passive"))
      (node (ref "U29") (pin "13") (pinfunction "VDD_13") (pintype "passive"))
      (node (ref "U29") (pin "14") (pinfunction "VDD_14") (pintype "passive"))
      (node (ref "U29") (pin "15") (pinfunction "VDD_15") (pintype "passive"))
      (node (ref "U29") (pin "16") (pinfunction "VDD_16") (pintype "passive"))
      (node (ref "U29") (pin "17") (pinfunction "VDD_17") (pintype "passive"))
      (node (ref "U29") (pin "18") (pinfunction "VDD_18") (pintype "passive"))
      (node (ref "U29") (pin "19") (pinfunction "VDD_19") (pintype "passive"))
      (node (ref "U29") (pin "2") (pinfunction "VDD_2") (pintype "passive"))
      (node (ref "U29") (pin "20") (pinfunction "VDD_20") (pintype "passive"))
      (node (ref "U29") (pin "21") (pinfunction "VDD_21") (pintype "passive"))
      (node (ref "U29") (pin "24") (pinfunction "VDD_24") (pintype "passive"))
      (node (ref "U29") (pin "25") (pinfunction "VDD_25") (pintype "passive"))
      (node (ref "U29") (pin "26") (pinfunction "VDD_26") (pintype "passive"))
      (node (ref "U29") (pin "27") (pinfunction "VDD_27") (pintype "passive"))
      (node (ref "U29") (pin "28") (pinfunction "VDD_28") (pintype "passive"))
      (node (ref "U29") (pin "29") (pinfunction "VDD_29") (pintype "passive"))
      (node (ref "U29") (pin "3") (pinfunction "VDD_3") (pintype "passive"))
      (node (ref "U29") (pin "30") (pinfunction "VDD_30") (pintype "passive"))
      (node (ref "U29") (pin "31") (pinfunction "VDD_31") (pintype "passive"))
      (node (ref "U29") (pin "32") (pinfunction "VDD_32") (pintype "passive"))
      (node (ref "U29") (pin "33") (pinfunction "VDD_33") (pintype "passive"))
      (node (ref "U29") (pin "34") (pinfunction "VDD_34") (pintype "passive"))
      (node (ref "U29") (pin "35") (pinfunction "VDD_35") (pintype "passive"))
      (node (ref "U29") (pin "4") (pinfunction "VDD_4") (pintype "passive"))
      (node (ref "U29") (pin "5") (pinfunction "VDD_5") (pintype "passive"))
      (node (ref "U29") (pin "6") (pinfunction "VDD_6") (pintype "passive"))
      (node (ref "U29") (pin "7") (pinfunction "VDD_7") (pintype "passive"))
      (node (ref "U29") (pin "8") (pinfunction "VDD_8") (pintype "passive"))
      (node (ref "U29") (pin "9") (pinfunction "VDD_9") (pintype "passive"))
      (node (ref "U33") (pin "34") (pinfunction "D_5_34") (pintype "passive"))
      (node (ref "U33") (pin "36") (pinfunction "V_4_36") (pintype "passive"))
    )
    (net (code "18") (name "/PWR17") (class "Default")
      (node (ref "U33") (pin "31") (pinfunction "D_6_31") (pintype "passive"))
      (node (ref "U33") (pin "33") (pinfunction "V_5_33") (pintype "passive"))
    )
    (net (code "19") (name "/PWR18") (class "Default")
      (node (ref "U33") (pin "28") (pinfunction "D_7_28") (pintype "passive"))
      (node (ref "U33") (pin "30") (pinfunction "V_6_30") (pintype "passive"))
    )
    (net (code "20") (name "/PWR19") (class "Default")
      (node (ref "U33") (pin "25") (pinfunction "D_8_25") (pintype "passive"))
      (node (ref "U33") (pin "27") (pinfunction "V_7_27") (pintype "passive"))
    )
    (net (code "21") (name "/PWR20") (class "Default")
      (node (ref "U33") (pin "22") (pinfunction "D_9_22") (pintype "passive"))
      (node (ref "U33") (pin "24") (pinfunction "V_8_24") (pintype "passive"))
    )
    (net (code "22") (name "/PWR21") (class "Default")
      (node (ref "U33") (pin "19") (pinfunction "D_10_19") (pintype "passive"))
      (node (ref "U33") (pin "21") (pinfunction "V_9_21") (pintype "passive"))
    )
    (net (code "23") (name "/PWR22") (class "Default")
      (node (ref "C187") (pin "1") (pinfunction "1_1") (pintype "passive"))
      (node (ref "U33") (pin "17") (pinfunction "VDD_17") (pintype "passive"))
    )
    (net (code "24") (name "/RX0_2") (class "Default")
      (node (ref "U33") (pin "12") (pinfunction "RX_0_12") (pintype "passive"))
    )
    (net (code "25") (name "/RX1_2") (class "Default")
      (node (ref "U33") (pin "14") (pinfunction "RX_1_14") (pintype "passive"))
    )
    (net (code "26") (name "/RX2_2") (class "Default")
      (node (ref "U33") (pin "16") (pinfunction "RX_2_16") (pintype "passive"))
    )
    (net (code "27") (name "/TX0_2") (class "Default")
      (node (ref "U33") (pin "11") (pinfunction "TX_0_11") (pintype "passive"))
    )
    (net (code "28") (name "/TX1_2") (class "Default")
      (node (ref "U33") (pin "13") (pinfunction "TX_1_13") (pintype "passive"))
    )
    (net (code "29") (name "/TX2_2") (class "Default")
      (node (ref "U33") (pin "15") (pinfunction "TX_2_15") (pintype "passive"))
    )
    (net (code "30") (name "unconnected-(U33-C_5-Pad35)") (class "Default")
      (node (ref "U33") (pin "35") (pinfunction "C_5_35") (pintype "passive"))
    )
    (net (code "31") (name "unconnected-(U33-C_6-Pad32)") (class "Default")
      (node (ref "U33") (pin "32") (pinfunction "C_6_32") (pintype "passive"))
    )
    (net (code "32") (name "unconnected-(U33-C_7-Pad29)") (class "Default")
      (node (ref "U33") (pin "29") (pinfunction "C_7_29") (pintype "passive"))
    )
    (net (code "33") (name "unconnected-(U33-C_8-Pad26)") (class "Default")
      (node (ref "U33") (pin "26") (pinfunction "C_8_26") (pintype "passive"))
    )
    (net (code "34") (name "unconnected-(U33-C_9-Pad23)") (class "Default")
      (node (ref "U33") (pin "23") (pinfunction "C_9_23") (pintype "passive"))
    )
    (net (code "35") (name "unconnected-(U33-C_10-Pad20)") (class "Default")
      (node (ref "U33") (pin "20") (pinfunction "C_10_20") (pintype "passive"))
    )
  )
)
